# clock.net
KiCad netlist of a schematic drawn in EAGLE
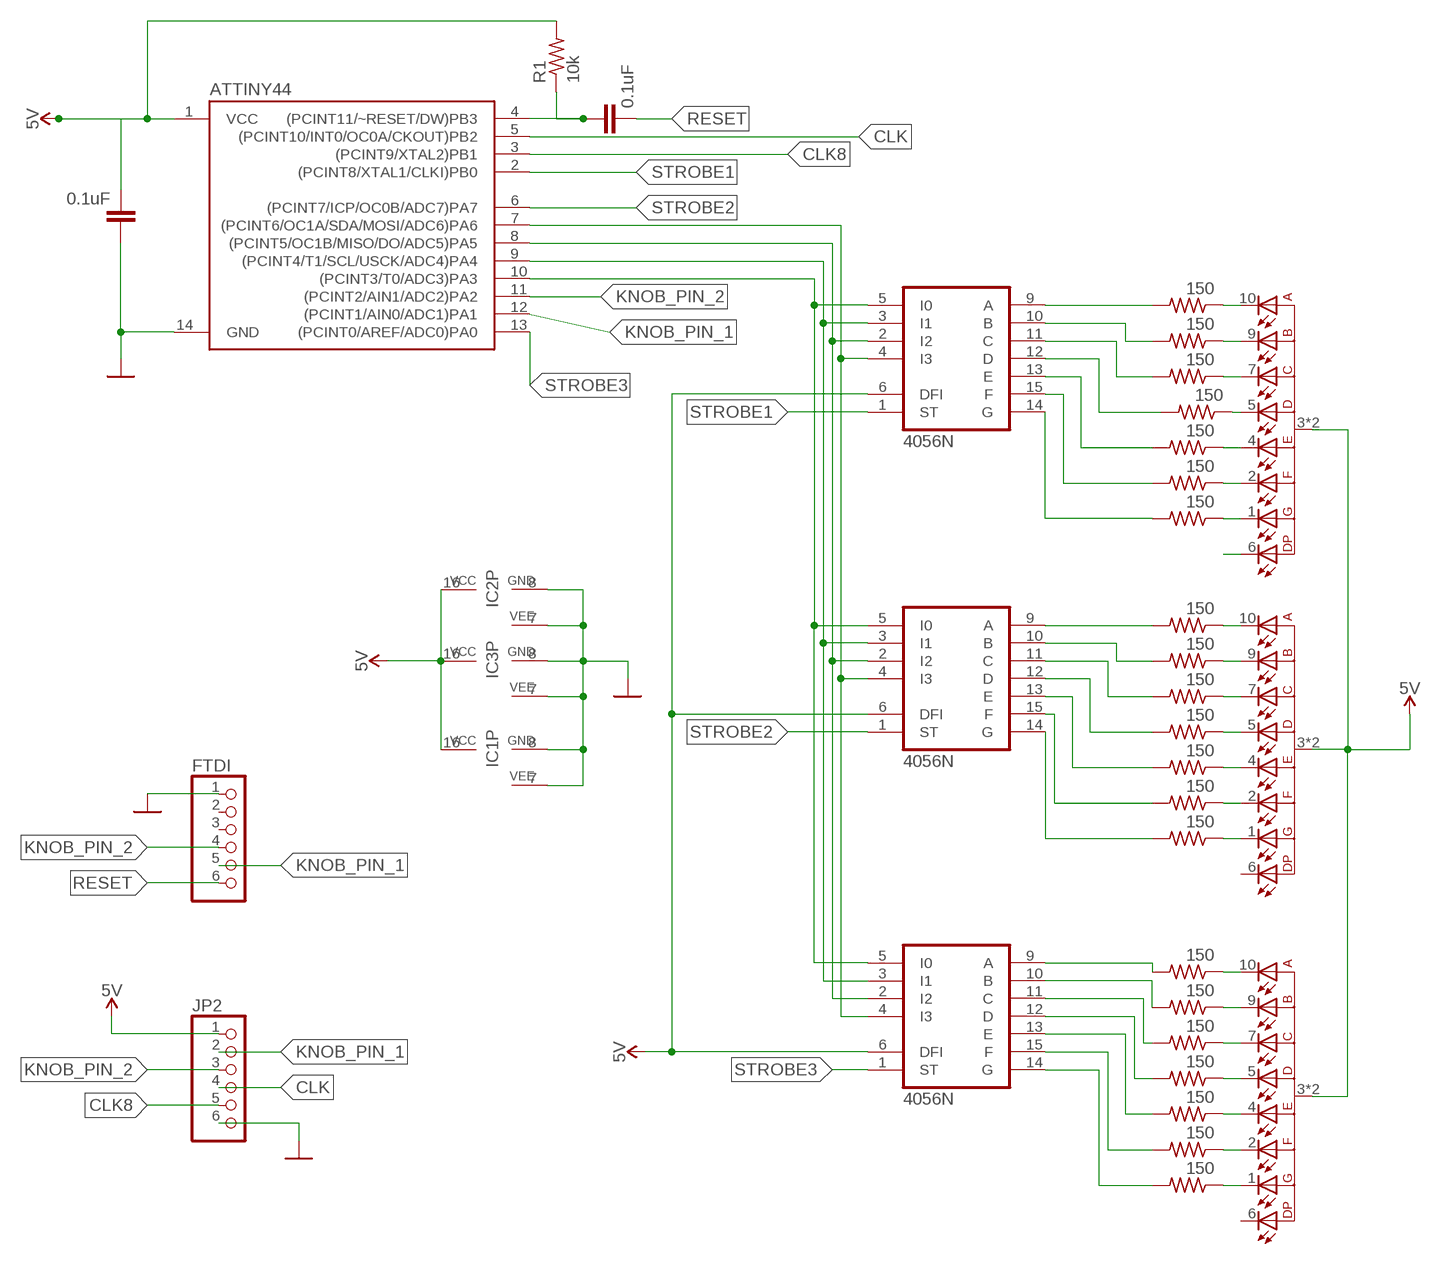
[diagram p0: schematic, sheet 1]

(export (version "E")
  (design (tool "Eeschema 10.0.6"))
  (components
    (comp (ref "ATTINY44")
      (value "ATTINY84ATTINY84-20PU")
      (footprint "eagle-import:DIP14")
      (libsource (lib "eagle-import") (part "ATTINY84ATTINY84-20PU"))
    )
    (comp (ref "C2")
      (value "0.1uF")
      (footprint "eagle-import:CAP-PTH-SMALL-KIT")
      (libsource (lib "eagle-import") (part "0.1UF-KIT-EZ-50V-20%"))
    )
    (comp (ref "C3")
      (value "0.1uF")
      (footprint "eagle-import:CAP-PTH-SMALL-KIT")
      (libsource (lib "eagle-import") (part "0.1UF-KIT-EZ-50V-20%"))
    )
    (comp (ref "D1")
      (value "157119S12801")
      (footprint "eagle-import:WL-T7DS_0.39INCH")
      (libsource (lib "eagle-import") (part "WL-T7DS_0.39INCH_COMMON-ANODE_157119S12801"))
    )
    (comp (ref "D2")
      (value "157119S12801")
      (footprint "eagle-import:WL-T7DS_0.39INCH")
      (libsource (lib "eagle-import") (part "WL-T7DS_0.39INCH_COMMON-ANODE_157119S12801"))
    )
    (comp (ref "D3")
      (value "157119S12801")
      (footprint "eagle-import:WL-T7DS_0.39INCH")
      (libsource (lib "eagle-import") (part "WL-T7DS_0.39INCH_COMMON-ANODE_157119S12801"))
    )
    (comp (ref "FTDI")
      (value "PINHD-1X6")
      (footprint "eagle-import:1X06")
      (libsource (lib "eagle-import") (part "PINHD-1X6"))
    )
    (comp (ref "IC1")
      (value "4056N")
      (footprint "eagle-import:DIL16")
      (libsource (lib "eagle-import") (part "4056N"))
    )
    (comp (ref "IC2")
      (value "4056N")
      (footprint "eagle-import:DIL16")
      (libsource (lib "eagle-import") (part "4056N"))
    )
    (comp (ref "IC3")
      (value "4056N")
      (footprint "eagle-import:DIL16")
      (libsource (lib "eagle-import") (part "4056N"))
    )
    (comp (ref "JP2")
      (value "PINHD-1X6")
      (footprint "eagle-import:1X06")
      (libsource (lib "eagle-import") (part "PINHD-1X6"))
    )
    (comp (ref "R1")
      (value "10k")
      (footprint "eagle-import:0207_12")
      (libsource (lib "eagle-import") (part "R-US_0207/12"))
    )
    (comp (ref "R2")
      (value "150")
      (footprint "eagle-import:0207_12")
      (libsource (lib "eagle-import") (part "R-US_0207/12"))
    )
    (comp (ref "R3")
      (value "150")
      (footprint "eagle-import:0207_12")
      (libsource (lib "eagle-import") (part "R-US_0207/12"))
    )
    (comp (ref "R4")
      (value "150")
      (footprint "eagle-import:0207_12")
      (libsource (lib "eagle-import") (part "R-US_0207/12"))
    )
    (comp (ref "R5")
      (value "150")
      (footprint "eagle-import:0207_12")
      (libsource (lib "eagle-import") (part "R-US_0207/12"))
    )
    (comp (ref "R6")
      (value "150")
      (footprint "eagle-import:0207_12")
      (libsource (lib "eagle-import") (part "R-US_0207/12"))
    )
    (comp (ref "R7")
      (value "150")
      (footprint "eagle-import:0207_12")
      (libsource (lib "eagle-import") (part "R-US_0207/12"))
    )
    (comp (ref "R8")
      (value "150")
      (footprint "eagle-import:0207_12")
      (libsource (lib "eagle-import") (part "R-US_0207/12"))
    )
    (comp (ref "R10")
      (value "150")
      (footprint "eagle-import:0207_12")
      (libsource (lib "eagle-import") (part "R-US_0207/12"))
    )
    (comp (ref "R11")
      (value "150")
      (footprint "eagle-import:0207_12")
      (libsource (lib "eagle-import") (part "R-US_0207/12"))
    )
    (comp (ref "R12")
      (value "150")
      (footprint "eagle-import:0207_12")
      (libsource (lib "eagle-import") (part "R-US_0207/12"))
    )
    (comp (ref "R13")
      (value "150")
      (footprint "eagle-import:0207_12")
      (libsource (lib "eagle-import") (part "R-US_0207/12"))
    )
    (comp (ref "R14")
      (value "150")
      (footprint "eagle-import:0207_12")
      (libsource (lib "eagle-import") (part "R-US_0207/12"))
    )
    (comp (ref "R15")
      (value "150")
      (footprint "eagle-import:0207_12")
      (libsource (lib "eagle-import") (part "R-US_0207/12"))
    )
    (comp (ref "R16")
      (value "150")
      (footprint "eagle-import:0207_12")
      (libsource (lib "eagle-import") (part "R-US_0207/12"))
    )
    (comp (ref "R18")
      (value "150")
      (footprint "eagle-import:0207_12")
      (libsource (lib "eagle-import") (part "R-US_0207/12"))
    )
    (comp (ref "R19")
      (value "150")
      (footprint "eagle-import:0207_12")
      (libsource (lib "eagle-import") (part "R-US_0207/12"))
    )
    (comp (ref "R20")
      (value "150")
      (footprint "eagle-import:0207_12")
      (libsource (lib "eagle-import") (part "R-US_0207/12"))
    )
    (comp (ref "R21")
      (value "150")
      (footprint "eagle-import:0207_12")
      (libsource (lib "eagle-import") (part "R-US_0207/12"))
    )
    (comp (ref "R22")
      (value "150")
      (footprint "eagle-import:0207_12")
      (libsource (lib "eagle-import") (part "R-US_0207/12"))
    )
    (comp (ref "R23")
      (value "150")
      (footprint "eagle-import:0207_12")
      (libsource (lib "eagle-import") (part "R-US_0207/12"))
    )
    (comp (ref "R24")
      (value "150")
      (footprint "eagle-import:0207_12")
      (libsource (lib "eagle-import") (part "R-US_0207/12"))
    )
  )
  (nets
    (net (code "1") (name "5V") (class "Default")
      (node (ref "ATTINY44") (pin "1") (pinfunction "VCC_1") (pintype "bidirectional"))
      (node (ref "C3") (pin "2") (pinfunction "2_2") (pintype "passive"))
      (node (ref "D1") (pin "3") (pinfunction "+_3") (pintype "passive"))
      (node (ref "D1") (pin "8") (pinfunction "+_8") (pintype "passive"))
      (node (ref "D2") (pin "3") (pinfunction "+_3") (pintype "passive"))
      (node (ref "D2") (pin "8") (pinfunction "+_8") (pintype "passive"))
      (node (ref "D3") (pin "3") (pinfunction "+_3") (pintype "passive"))
      (node (ref "D3") (pin "8") (pinfunction "+_8") (pintype "passive"))
      (node (ref "IC1") (pin "16") (pinfunction "VCC_16") (pintype "power_in"))
      (node (ref "IC1") (pin "6") (pinfunction "DFI_6") (pintype "input"))
      (node (ref "IC2") (pin "16") (pinfunction "VCC_16") (pintype "power_in"))
      (node (ref "IC2") (pin "6") (pinfunction "DFI_6") (pintype "input"))
      (node (ref "IC3") (pin "16") (pinfunction "VCC_16") (pintype "power_in"))
      (node (ref "IC3") (pin "6") (pinfunction "DFI_6") (pintype "input"))
      (node (ref "JP2") (pin "1") (pinfunction "1_1") (pintype "passive"))
      (node (ref "R1") (pin "2") (pinfunction "2_2") (pintype "passive"))
    )
    (net (code "2") (name "CLK") (class "Default")
      (node (ref "ATTINY44") (pin "5") (pinfunction "(PCINT10/INT0/OC0A/CKOUT)PB2_5") (pintype "bidirectional"))
      (node (ref "JP2") (pin "4") (pinfunction "4_4") (pintype "passive"))
    )
    (net (code "3") (name "CLK8") (class "Default")
      (node (ref "ATTINY44") (pin "3") (pinfunction "(PCINT9/XTAL2)PB1_3") (pintype "bidirectional"))
      (node (ref "JP2") (pin "5") (pinfunction "5_5") (pintype "passive"))
    )
    (net (code "4") (name "GND") (class "Default")
      (node (ref "ATTINY44") (pin "14") (pinfunction "GND_14") (pintype "bidirectional"))
      (node (ref "C3") (pin "1") (pinfunction "1_1") (pintype "passive"))
      (node (ref "FTDI") (pin "1") (pinfunction "1_1") (pintype "passive"))
      (node (ref "IC1") (pin "7") (pinfunction "VEE_7") (pintype "power_in"))
      (node (ref "IC1") (pin "8") (pinfunction "GND_8") (pintype "power_in"))
      (node (ref "IC2") (pin "7") (pinfunction "VEE_7") (pintype "power_in"))
      (node (ref "IC2") (pin "8") (pinfunction "GND_8") (pintype "power_in"))
      (node (ref "IC3") (pin "7") (pinfunction "VEE_7") (pintype "power_in"))
      (node (ref "IC3") (pin "8") (pinfunction "GND_8") (pintype "power_in"))
      (node (ref "JP2") (pin "6") (pinfunction "6_6") (pintype "passive"))
    )
    (net (code "5") (name "KNOB_PIN_1") (class "Default")
      (node (ref "ATTINY44") (pin "12") (pinfunction "(PCINT1/AIN0/ADC1)PA1_12") (pintype "bidirectional"))
      (node (ref "FTDI") (pin "5") (pinfunction "5_5") (pintype "passive"))
      (node (ref "JP2") (pin "2") (pinfunction "2_2") (pintype "passive"))
    )
    (net (code "6") (name "KNOB_PIN_2") (class "Default")
      (node (ref "ATTINY44") (pin "11") (pinfunction "(PCINT2/AIN1/ADC2)PA2_11") (pintype "bidirectional"))
      (node (ref "FTDI") (pin "4") (pinfunction "4_4") (pintype "passive"))
      (node (ref "JP2") (pin "3") (pinfunction "3_3") (pintype "passive"))
    )
    (net (code "7") (name "Net-(ATTINY44-(PCINT3{slash}T0{slash}ADC3)PA3)") (class "Default")
      (node (ref "ATTINY44") (pin "10") (pinfunction "(PCINT3/T0/ADC3)PA3_10") (pintype "bidirectional"))
      (node (ref "IC1") (pin "5") (pinfunction "I0_5") (pintype "input"))
      (node (ref "IC2") (pin "5") (pinfunction "I0_5") (pintype "input"))
      (node (ref "IC3") (pin "5") (pinfunction "I0_5") (pintype "input"))
    )
    (net (code "8") (name "Net-(ATTINY44-(PCINT4{slash}T1{slash}SCL{slash}USCK{slash}ADC4)PA4)") (class "Default")
      (node (ref "ATTINY44") (pin "9") (pinfunction "(PCINT4/T1/SCL/USCK/ADC4)PA4_9") (pintype "bidirectional"))
      (node (ref "IC1") (pin "3") (pinfunction "I1_3") (pintype "input"))
      (node (ref "IC2") (pin "3") (pinfunction "I1_3") (pintype "input"))
      (node (ref "IC3") (pin "3") (pinfunction "I1_3") (pintype "input"))
    )
    (net (code "9") (name "Net-(ATTINY44-(PCINT5{slash}OC1B{slash}MISO{slash}DO{slash}ADC5)PA5)") (class "Default")
      (node (ref "ATTINY44") (pin "8") (pinfunction "(PCINT5/OC1B/MISO/DO/ADC5)PA5_8") (pintype "bidirectional"))
      (node (ref "IC1") (pin "2") (pinfunction "I2_2") (pintype "input"))
      (node (ref "IC2") (pin "2") (pinfunction "I2_2") (pintype "input"))
      (node (ref "IC3") (pin "2") (pinfunction "I2_2") (pintype "input"))
    )
    (net (code "10") (name "Net-(ATTINY44-(PCINT6{slash}OC1A{slash}SDA{slash}MOSI{slash}ADC6)PA6)") (class "Default")
      (node (ref "ATTINY44") (pin "7") (pinfunction "(PCINT6/OC1A/SDA/MOSI/ADC6)PA6_7") (pintype "bidirectional"))
      (node (ref "IC1") (pin "4") (pinfunction "I3_4") (pintype "input"))
      (node (ref "IC2") (pin "4") (pinfunction "I3_4") (pintype "input"))
      (node (ref "IC3") (pin "4") (pinfunction "I3_4") (pintype "input"))
    )
    (net (code "11") (name "Net-(ATTINY44-(PCINT11{slash}~{RESET{slash}DW})PB3)") (class "Default")
      (node (ref "ATTINY44") (pin "4") (pinfunction "(PCINT11/~{RESET/DW})PB3_4") (pintype "bidirectional"))
      (node (ref "C2") (pin "1") (pinfunction "1_1") (pintype "passive"))
      (node (ref "R1") (pin "1") (pinfunction "1_1") (pintype "passive"))
    )
    (net (code "12") (name "Net-(D1-1)") (class "Default")
      (node (ref "D1") (pin "4") (pinfunction "1_4") (pintype "passive"))
      (node (ref "R6") (pin "1") (pinfunction "1_1") (pintype "passive"))
    )
    (net (code "13") (name "Net-(D1-2)") (class "Default")
      (node (ref "D1") (pin "5") (pinfunction "2_5") (pintype "passive"))
      (node (ref "R5") (pin "1") (pinfunction "1_1") (pintype "passive"))
    )
    (net (code "14") (name "Net-(D1-4)") (class "Default")
      (node (ref "D1") (pin "7") (pinfunction "4_7") (pintype "passive"))
      (node (ref "R4") (pin "1") (pinfunction "1_1") (pintype "passive"))
    )
    (net (code "15") (name "Net-(D1-6)") (class "Default")
      (node (ref "D1") (pin "9") (pinfunction "6_9") (pintype "passive"))
      (node (ref "R3") (pin "1") (pinfunction "1_1") (pintype "passive"))
    )
    (net (code "16") (name "Net-(D1-7)") (class "Default")
      (node (ref "D1") (pin "10") (pinfunction "7_10") (pintype "passive"))
      (node (ref "R2") (pin "1") (pinfunction "1_1") (pintype "passive"))
    )
    (net (code "17") (name "Net-(D1-9)") (class "Default")
      (node (ref "D1") (pin "2") (pinfunction "9_2") (pintype "passive"))
      (node (ref "R7") (pin "1") (pinfunction "1_1") (pintype "passive"))
    )
    (net (code "18") (name "Net-(D1-10)") (class "Default")
      (node (ref "D1") (pin "1") (pinfunction "10_1") (pintype "passive"))
      (node (ref "R8") (pin "1") (pinfunction "1_1") (pintype "passive"))
    )
    (net (code "19") (name "Net-(D2-1)") (class "Default")
      (node (ref "D2") (pin "4") (pinfunction "1_4") (pintype "passive"))
      (node (ref "R22") (pin "1") (pinfunction "1_1") (pintype "passive"))
    )
    (net (code "20") (name "Net-(D2-2)") (class "Default")
      (node (ref "D2") (pin "5") (pinfunction "2_5") (pintype "passive"))
      (node (ref "R21") (pin "1") (pinfunction "1_1") (pintype "passive"))
    )
    (net (code "21") (name "Net-(D2-4)") (class "Default")
      (node (ref "D2") (pin "7") (pinfunction "4_7") (pintype "passive"))
      (node (ref "R20") (pin "1") (pinfunction "1_1") (pintype "passive"))
    )
    (net (code "22") (name "Net-(D2-6)") (class "Default")
      (node (ref "D2") (pin "9") (pinfunction "6_9") (pintype "passive"))
      (node (ref "R19") (pin "1") (pinfunction "1_1") (pintype "passive"))
    )
    (net (code "23") (name "Net-(D2-7)") (class "Default")
      (node (ref "D2") (pin "10") (pinfunction "7_10") (pintype "passive"))
      (node (ref "R18") (pin "1") (pinfunction "1_1") (pintype "passive"))
    )
    (net (code "24") (name "Net-(D2-9)") (class "Default")
      (node (ref "D2") (pin "2") (pinfunction "9_2") (pintype "passive"))
      (node (ref "R23") (pin "1") (pinfunction "1_1") (pintype "passive"))
    )
    (net (code "25") (name "Net-(D2-10)") (class "Default")
      (node (ref "D2") (pin "1") (pinfunction "10_1") (pintype "passive"))
      (node (ref "R24") (pin "1") (pinfunction "1_1") (pintype "passive"))
    )
    (net (code "26") (name "Net-(D3-1)") (class "Default")
      (node (ref "D3") (pin "4") (pinfunction "1_4") (pintype "passive"))
      (node (ref "R14") (pin "1") (pinfunction "1_1") (pintype "passive"))
    )
    (net (code "27") (name "Net-(D3-2)") (class "Default")
      (node (ref "D3") (pin "5") (pinfunction "2_5") (pintype "passive"))
      (node (ref "R13") (pin "1") (pinfunction "1_1") (pintype "passive"))
    )
    (net (code "28") (name "Net-(D3-4)") (class "Default")
      (node (ref "D3") (pin "7") (pinfunction "4_7") (pintype "passive"))
      (node (ref "R12") (pin "1") (pinfunction "1_1") (pintype "passive"))
    )
    (net (code "29") (name "Net-(D3-6)") (class "Default")
      (node (ref "D3") (pin "9") (pinfunction "6_9") (pintype "passive"))
      (node (ref "R11") (pin "1") (pinfunction "1_1") (pintype "passive"))
    )
    (net (code "30") (name "Net-(D3-7)") (class "Default")
      (node (ref "D3") (pin "10") (pinfunction "7_10") (pintype "passive"))
      (node (ref "R10") (pin "1") (pinfunction "1_1") (pintype "passive"))
    )
    (net (code "31") (name "Net-(D3-9)") (class "Default")
      (node (ref "D3") (pin "2") (pinfunction "9_2") (pintype "passive"))
      (node (ref "R15") (pin "1") (pinfunction "1_1") (pintype "passive"))
    )
    (net (code "32") (name "Net-(D3-10)") (class "Default")
      (node (ref "D3") (pin "1") (pinfunction "10_1") (pintype "passive"))
      (node (ref "R16") (pin "1") (pinfunction "1_1") (pintype "passive"))
    )
    (net (code "33") (name "Net-(IC1A-A)") (class "Default")
      (node (ref "IC1") (pin "9") (pinfunction "A_9") (pintype "output"))
      (node (ref "R18") (pin "2") (pinfunction "2_2") (pintype "passive"))
    )
    (net (code "34") (name "Net-(IC1A-B)") (class "Default")
      (node (ref "IC1") (pin "10") (pinfunction "B_10") (pintype "output"))
      (node (ref "R19") (pin "2") (pinfunction "2_2") (pintype "passive"))
    )
    (net (code "35") (name "Net-(IC1A-C)") (class "Default")
      (node (ref "IC1") (pin "11") (pinfunction "C_11") (pintype "output"))
      (node (ref "R20") (pin "2") (pinfunction "2_2") (pintype "passive"))
    )
    (net (code "36") (name "Net-(IC1A-D)") (class "Default")
      (node (ref "IC1") (pin "12") (pinfunction "D_12") (pintype "output"))
      (node (ref "R21") (pin "2") (pinfunction "2_2") (pintype "passive"))
    )
    (net (code "37") (name "Net-(IC1A-E)") (class "Default")
      (node (ref "IC1") (pin "13") (pinfunction "E_13") (pintype "output"))
      (node (ref "R22") (pin "2") (pinfunction "2_2") (pintype "passive"))
    )
    (net (code "38") (name "Net-(IC1A-F)") (class "Default")
      (node (ref "IC1") (pin "15") (pinfunction "F_15") (pintype "output"))
      (node (ref "R23") (pin "2") (pinfunction "2_2") (pintype "passive"))
    )
    (net (code "39") (name "Net-(IC1A-G)") (class "Default")
      (node (ref "IC1") (pin "14") (pinfunction "G_14") (pintype "output"))
      (node (ref "R24") (pin "2") (pinfunction "2_2") (pintype "passive"))
    )
    (net (code "40") (name "Net-(IC2A-A)") (class "Default")
      (node (ref "IC2") (pin "9") (pinfunction "A_9") (pintype "output"))
      (node (ref "R2") (pin "2") (pinfunction "2_2") (pintype "passive"))
    )
    (net (code "41") (name "Net-(IC2A-B)") (class "Default")
      (node (ref "IC2") (pin "10") (pinfunction "B_10") (pintype "output"))
      (node (ref "R3") (pin "2") (pinfunction "2_2") (pintype "passive"))
    )
    (net (code "42") (name "Net-(IC2A-C)") (class "Default")
      (node (ref "IC2") (pin "11") (pinfunction "C_11") (pintype "output"))
      (node (ref "R4") (pin "2") (pinfunction "2_2") (pintype "passive"))
    )
    (net (code "43") (name "Net-(IC2A-D)") (class "Default")
      (node (ref "IC2") (pin "12") (pinfunction "D_12") (pintype "output"))
      (node (ref "R5") (pin "2") (pinfunction "2_2") (pintype "passive"))
    )
    (net (code "44") (name "Net-(IC2A-E)") (class "Default")
      (node (ref "IC2") (pin "13") (pinfunction "E_13") (pintype "output"))
      (node (ref "R6") (pin "2") (pinfunction "2_2") (pintype "passive"))
    )
    (net (code "45") (name "Net-(IC2A-F)") (class "Default")
      (node (ref "IC2") (pin "15") (pinfunction "F_15") (pintype "output"))
      (node (ref "R7") (pin "2") (pinfunction "2_2") (pintype "passive"))
    )
    (net (code "46") (name "Net-(IC2A-G)") (class "Default")
      (node (ref "IC2") (pin "14") (pinfunction "G_14") (pintype "output"))
      (node (ref "R8") (pin "2") (pinfunction "2_2") (pintype "passive"))
    )
    (net (code "47") (name "Net-(IC3A-A)") (class "Default")
      (node (ref "IC3") (pin "9") (pinfunction "A_9") (pintype "output"))
      (node (ref "R10") (pin "2") (pinfunction "2_2") (pintype "passive"))
    )
    (net (code "48") (name "Net-(IC3A-B)") (class "Default")
      (node (ref "IC3") (pin "10") (pinfunction "B_10") (pintype "output"))
      (node (ref "R11") (pin "2") (pinfunction "2_2") (pintype "passive"))
    )
    (net (code "49") (name "Net-(IC3A-C)") (class "Default")
      (node (ref "IC3") (pin "11") (pinfunction "C_11") (pintype "output"))
      (node (ref "R12") (pin "2") (pinfunction "2_2") (pintype "passive"))
    )
    (net (code "50") (name "Net-(IC3A-D)") (class "Default")
      (node (ref "IC3") (pin "12") (pinfunction "D_12") (pintype "output"))
      (node (ref "R13") (pin "2") (pinfunction "2_2") (pintype "passive"))
    )
    (net (code "51") (name "Net-(IC3A-E)") (class "Default")
      (node (ref "IC3") (pin "13") (pinfunction "E_13") (pintype "output"))
      (node (ref "R14") (pin "2") (pinfunction "2_2") (pintype "passive"))
    )
    (net (code "52") (name "Net-(IC3A-F)") (class "Default")
      (node (ref "IC3") (pin "15") (pinfunction "F_15") (pintype "output"))
      (node (ref "R15") (pin "2") (pinfunction "2_2") (pintype "passive"))
    )
    (net (code "53") (name "Net-(IC3A-G)") (class "Default")
      (node (ref "IC3") (pin "14") (pinfunction "G_14") (pintype "output"))
      (node (ref "R16") (pin "2") (pinfunction "2_2") (pintype "passive"))
    )
    (net (code "54") (name "RESET") (class "Default")
      (node (ref "C2") (pin "2") (pinfunction "2_2") (pintype "passive"))
      (node (ref "FTDI") (pin "6") (pinfunction "6_6") (pintype "passive"))
    )
    (net (code "55") (name "STROBE1") (class "Default")
      (node (ref "ATTINY44") (pin "2") (pinfunction "(PCINT8/XTAL1/CLKI)PB0_2") (pintype "bidirectional"))
      (node (ref "IC2") (pin "1") (pinfunction "ST_1") (pintype "input"))
    )
    (net (code "56") (name "STROBE2") (class "Default")
      (node (ref "ATTINY44") (pin "6") (pinfunction "(PCINT7/ICP/OC0B/ADC7)PA7_6") (pintype "bidirectional"))
      (node (ref "IC3") (pin "1") (pinfunction "ST_1") (pintype "input"))
    )
    (net (code "57") (name "STROBE3") (class "Default")
      (node (ref "ATTINY44") (pin "13") (pinfunction "(PCINT0/AREF/ADC0)PA0_13") (pintype "bidirectional"))
      (node (ref "IC1") (pin "1") (pinfunction "ST_1") (pintype "input"))
    )
    (net (code "58") (name "unconnected-(D1-5-Pad6)") (class "Default")
      (node (ref "D1") (pin "6") (pinfunction "5_6") (pintype "passive"))
    )
    (net (code "59") (name "unconnected-(D2-5-Pad6)") (class "Default")
      (node (ref "D2") (pin "6") (pinfunction "5_6") (pintype "passive"))
    )
    (net (code "60") (name "unconnected-(D3-5-Pad6)") (class "Default")
      (node (ref "D3") (pin "6") (pinfunction "5_6") (pintype "passive"))
    )
    (net (code "61") (name "unconnected-(FTDI-Pad2)") (class "Default")
      (node (ref "FTDI") (pin "2") (pinfunction "2_2") (pintype "passive"))
    )
    (net (code "62") (name "unconnected-(FTDI-Pad3)") (class "Default")
      (node (ref "FTDI") (pin "3") (pinfunction "3_3") (pintype "passive"))
    )
  )
)
